# irisc.net
KiCad netlist of a schematic drawn in EAGLE
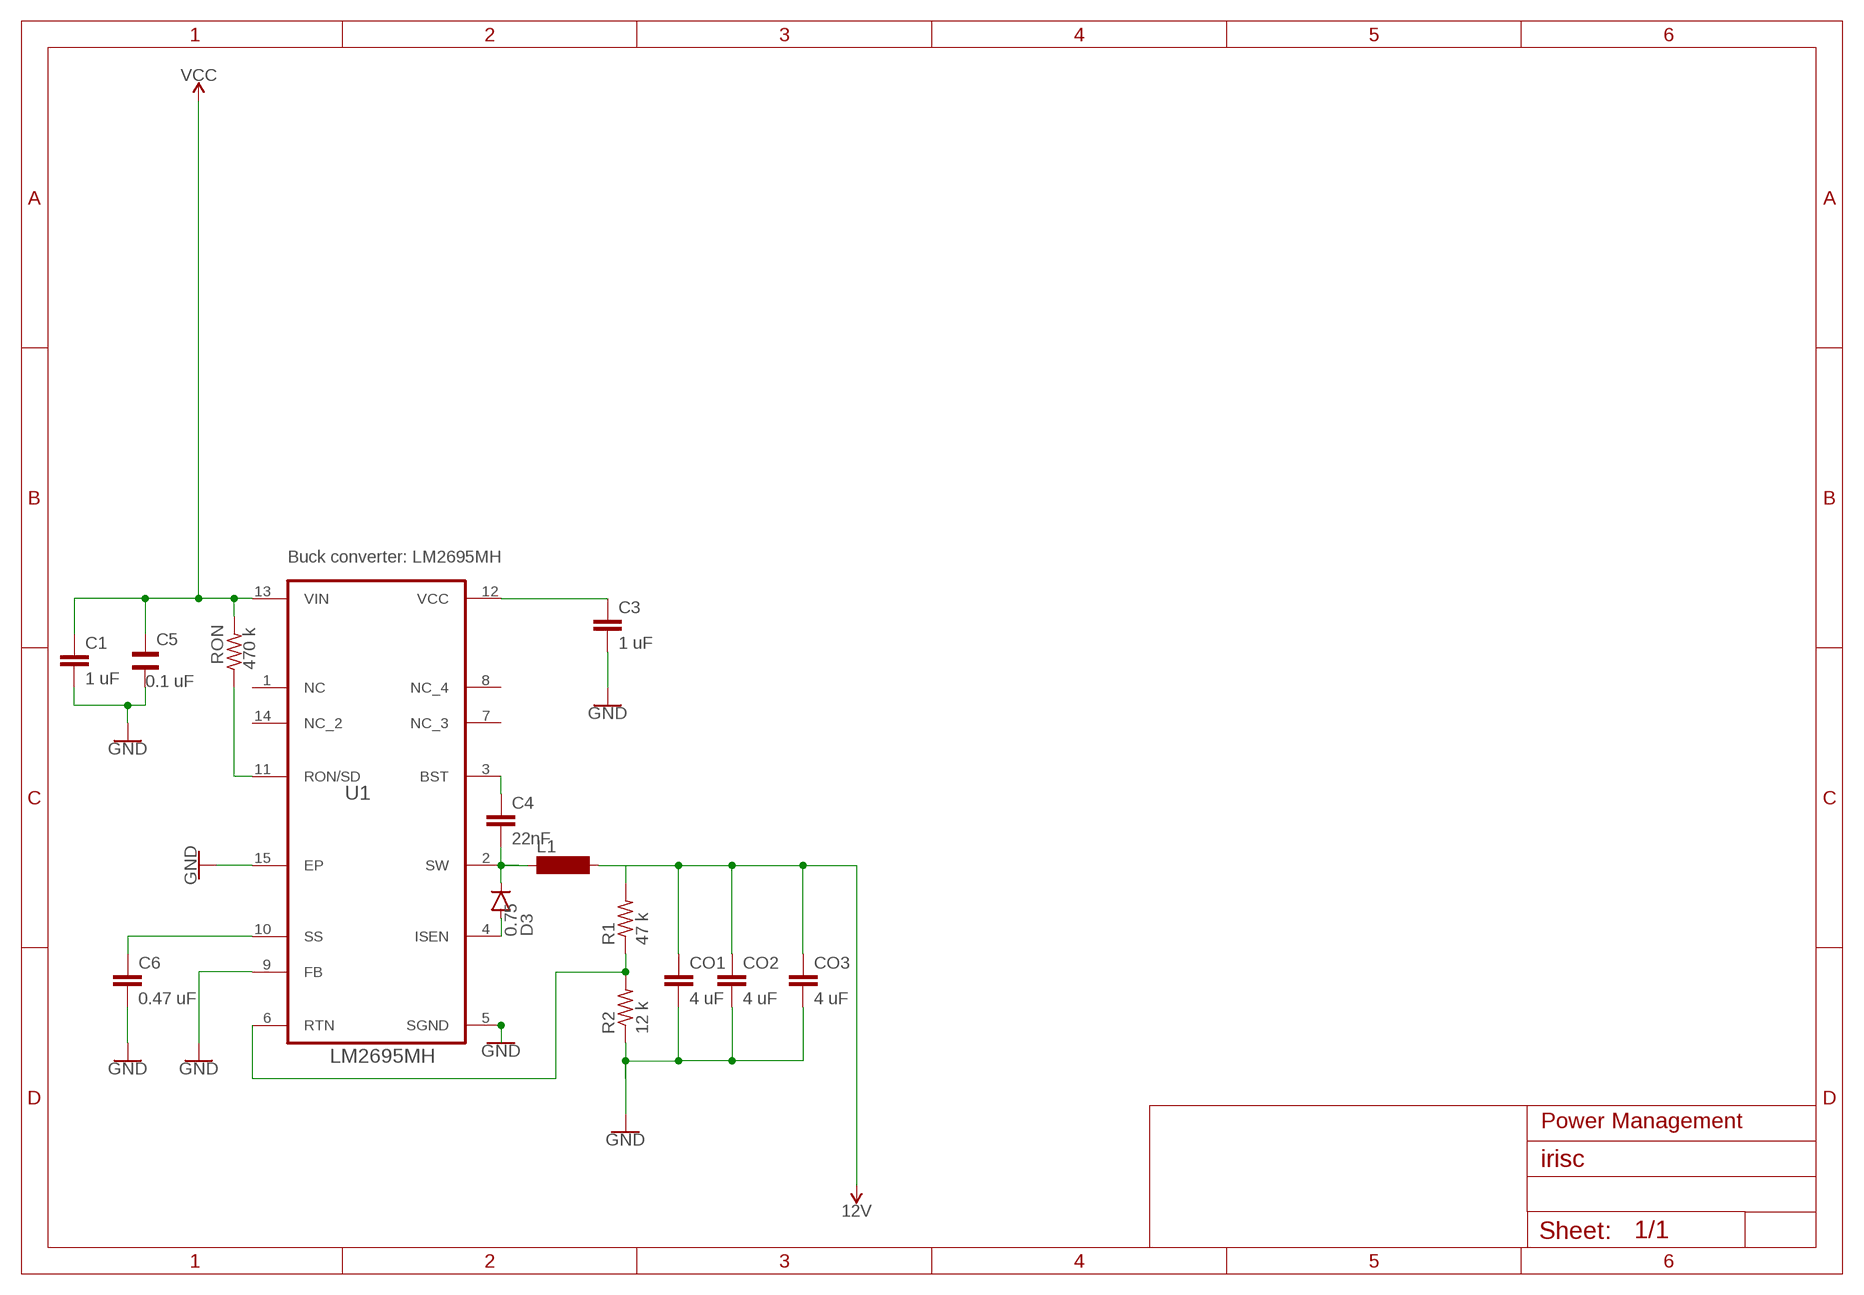
[diagram p0: schematic, sheet 1]

(export (version "E")
  (design (tool "Eeschema 10.0.6"))
  (components
    (comp (ref "C1")
      (value "1 uF")
      (footprint "eagle-import:C1210")
      (libsource (lib "eagle-import") (part "CC1210"))
    )
    (comp (ref "C3")
      (value "1 uF")
      (footprint "eagle-import:C1210")
      (libsource (lib "eagle-import") (part "CC1210"))
    )
    (comp (ref "C4")
      (value "22nF")
      (footprint "eagle-import:C1206")
      (libsource (lib "eagle-import") (part "CC1206"))
    )
    (comp (ref "C5")
      (value "0.1 uF")
      (footprint "eagle-import:WCAP-CSGP_0805_REFLOW")
      (fields (field (name "SPICEPREFIX") "C"))
      (libsource (lib "eagle-import") (part "WCAP-CSGP_0805_REFLOW_885012006082"))
    )
    (comp (ref "C6")
      (value "0.47 uF")
      (footprint "eagle-import:C1210")
      (libsource (lib "eagle-import") (part "CC1210"))
    )
    (comp (ref "CO1")
      (value "4 uF")
      (footprint "eagle-import:C1812")
      (libsource (lib "eagle-import") (part "CC1812"))
    )
    (comp (ref "CO2")
      (value "4 uF")
      (footprint "eagle-import:C1812")
      (libsource (lib "eagle-import") (part "CC1812"))
    )
    (comp (ref "CO3")
      (value "4 uF")
      (footprint "eagle-import:C1812")
      (libsource (lib "eagle-import") (part "CC1812"))
    )
    (comp (ref "D3")
      (value "0.75")
      (footprint "eagle-import:DIODE-1N4001-KIT")
      (fields (field (name "SPICEPREFIX") "D"))
      (libsource (lib "eagle-import") (part "DIODE"))
    )
    (comp (ref "L1")
      (value "BS11")
      (footprint "eagle-import:BS11")
      (libsource (lib "eagle-import") (part "BS11"))
    )
    (comp (ref "R1")
      (value "47 k")
      (footprint "eagle-import:0805-THM")
      (fields (field (name "SPICEPREFIX") "R"))
      (libsource (lib "eagle-import") (part "FLIPFLOP-RES"))
    )
    (comp (ref "R2")
      (value "12 k")
      (footprint "eagle-import:0805-THM")
      (fields (field (name "SPICEPREFIX") "R"))
      (libsource (lib "eagle-import") (part "FLIPFLOP-RES"))
    )
    (comp (ref "RON")
      (value "470 k")
      (footprint "eagle-import:0805-THM")
      (fields (field (name "SPICEPREFIX") "R"))
      (libsource (lib "eagle-import") (part "FLIPFLOP-RES"))
    )
    (comp (ref "U1")
      (value "LM2695MH")
      (footprint "eagle-import:SOP65P640X110-15N")
      (fields
        (field (name "DIGI-KEY_PART_NUMBER") "LM2695MH/NOPB-ND")
        (field (name "MF") "Texas Instruments")
        (field (name "MP") "LM2695MH/NOPB")
      )
      (libsource (lib "eagle-import") (part "LM2695MH"))
    )
  )
  (nets
    (net (code "1") (name "12V") (class "Default")
      (node (ref "CO1") (pin "1") (pinfunction "1_1") (pintype "passive"))
      (node (ref "CO2") (pin "1") (pinfunction "1_1") (pintype "passive"))
      (node (ref "CO3") (pin "1") (pinfunction "1_1") (pintype "passive"))
      (node (ref "L1") (pin "2") (pinfunction "2_2") (pintype "passive"))
      (node (ref "R1") (pin "2") (pinfunction "2_2") (pintype "passive"))
    )
    (net (code "2") (name "GND") (class "Default")
      (node (ref "C1") (pin "2") (pinfunction "2_2") (pintype "passive"))
      (node (ref "C3") (pin "2") (pinfunction "2_2") (pintype "passive"))
      (node (ref "C5") (pin "1") (pinfunction "1_1") (pintype "passive"))
      (node (ref "C6") (pin "2") (pinfunction "2_2") (pintype "passive"))
      (node (ref "CO1") (pin "2") (pinfunction "2_2") (pintype "passive"))
      (node (ref "CO2") (pin "2") (pinfunction "2_2") (pintype "passive"))
      (node (ref "CO3") (pin "2") (pinfunction "2_2") (pintype "passive"))
      (node (ref "R2") (pin "1") (pinfunction "1_1") (pintype "passive"))
      (node (ref "U1") (pin "15") (pinfunction "EP_15") (pintype "passive"))
      (node (ref "U1") (pin "5") (pinfunction "SGND_5") (pintype "passive"))
      (node (ref "U1") (pin "9") (pinfunction "FB_9") (pintype "passive"))
    )
    (net (code "3") (name "Net-(U1-BST)") (class "Default")
      (node (ref "C4") (pin "1") (pinfunction "1_1") (pintype "passive"))
      (node (ref "U1") (pin "3") (pinfunction "BST_3") (pintype "passive"))
    )
    (net (code "4") (name "Net-(U1-ISEN)") (class "Default")
      (node (ref "D3") (pin "A") (pinfunction "A_A") (pintype "passive"))
      (node (ref "U1") (pin "4") (pinfunction "ISEN_4") (pintype "passive"))
    )
    (net (code "5") (name "Net-(U1-RON{slash}SD)") (class "Default")
      (node (ref "RON") (pin "1") (pinfunction "1_1") (pintype "passive"))
      (node (ref "U1") (pin "11") (pinfunction "RON/SD_11") (pintype "passive"))
    )
    (net (code "6") (name "Net-(U1-RTN)") (class "Default")
      (node (ref "R1") (pin "1") (pinfunction "1_1") (pintype "passive"))
      (node (ref "R2") (pin "2") (pinfunction "2_2") (pintype "passive"))
      (node (ref "U1") (pin "6") (pinfunction "RTN_6") (pintype "passive"))
    )
    (net (code "7") (name "Net-(U1-SS)") (class "Default")
      (node (ref "C6") (pin "1") (pinfunction "1_1") (pintype "passive"))
      (node (ref "U1") (pin "10") (pinfunction "SS_10") (pintype "passive"))
    )
    (net (code "8") (name "Net-(U1-SW)") (class "Default")
      (node (ref "C4") (pin "2") (pinfunction "2_2") (pintype "passive"))
      (node (ref "D3") (pin "C") (pinfunction "C_C") (pintype "passive"))
      (node (ref "L1") (pin "1") (pinfunction "1_1") (pintype "passive"))
      (node (ref "U1") (pin "2") (pinfunction "SW_2") (pintype "output"))
    )
    (net (code "9") (name "Net-(U1-VCC)") (class "Default")
      (node (ref "C3") (pin "1") (pinfunction "1_1") (pintype "passive"))
      (node (ref "U1") (pin "12") (pinfunction "VCC_12") (pintype "passive"))
    )
    (net (code "10") (name "VCC") (class "Default")
      (node (ref "C1") (pin "1") (pinfunction "1_1") (pintype "passive"))
      (node (ref "C5") (pin "2") (pinfunction "2_2") (pintype "passive"))
      (node (ref "RON") (pin "2") (pinfunction "2_2") (pintype "passive"))
      (node (ref "U1") (pin "13") (pinfunction "VIN_13") (pintype "input"))
    )
    (net (code "11") (name "unconnected-(U1-NC-Pad1)") (class "Default")
      (node (ref "U1") (pin "1") (pinfunction "NC_1") (pintype "passive"))
    )
    (net (code "12") (name "unconnected-(U1-NC_2-Pad14)") (class "Default")
      (node (ref "U1") (pin "14") (pinfunction "NC_2_14") (pintype "passive"))
    )
    (net (code "13") (name "unconnected-(U1-NC_3-Pad7)") (class "Default")
      (node (ref "U1") (pin "7") (pinfunction "NC_3_7") (pintype "passive"))
    )
    (net (code "14") (name "unconnected-(U1-NC_4-Pad8)") (class "Default")
      (node (ref "U1") (pin "8") (pinfunction "NC_4_8") (pintype "passive"))
    )
  )
)
